# 3_phy1.net
KiCad netlist of a schematic drawn in Altium Designer
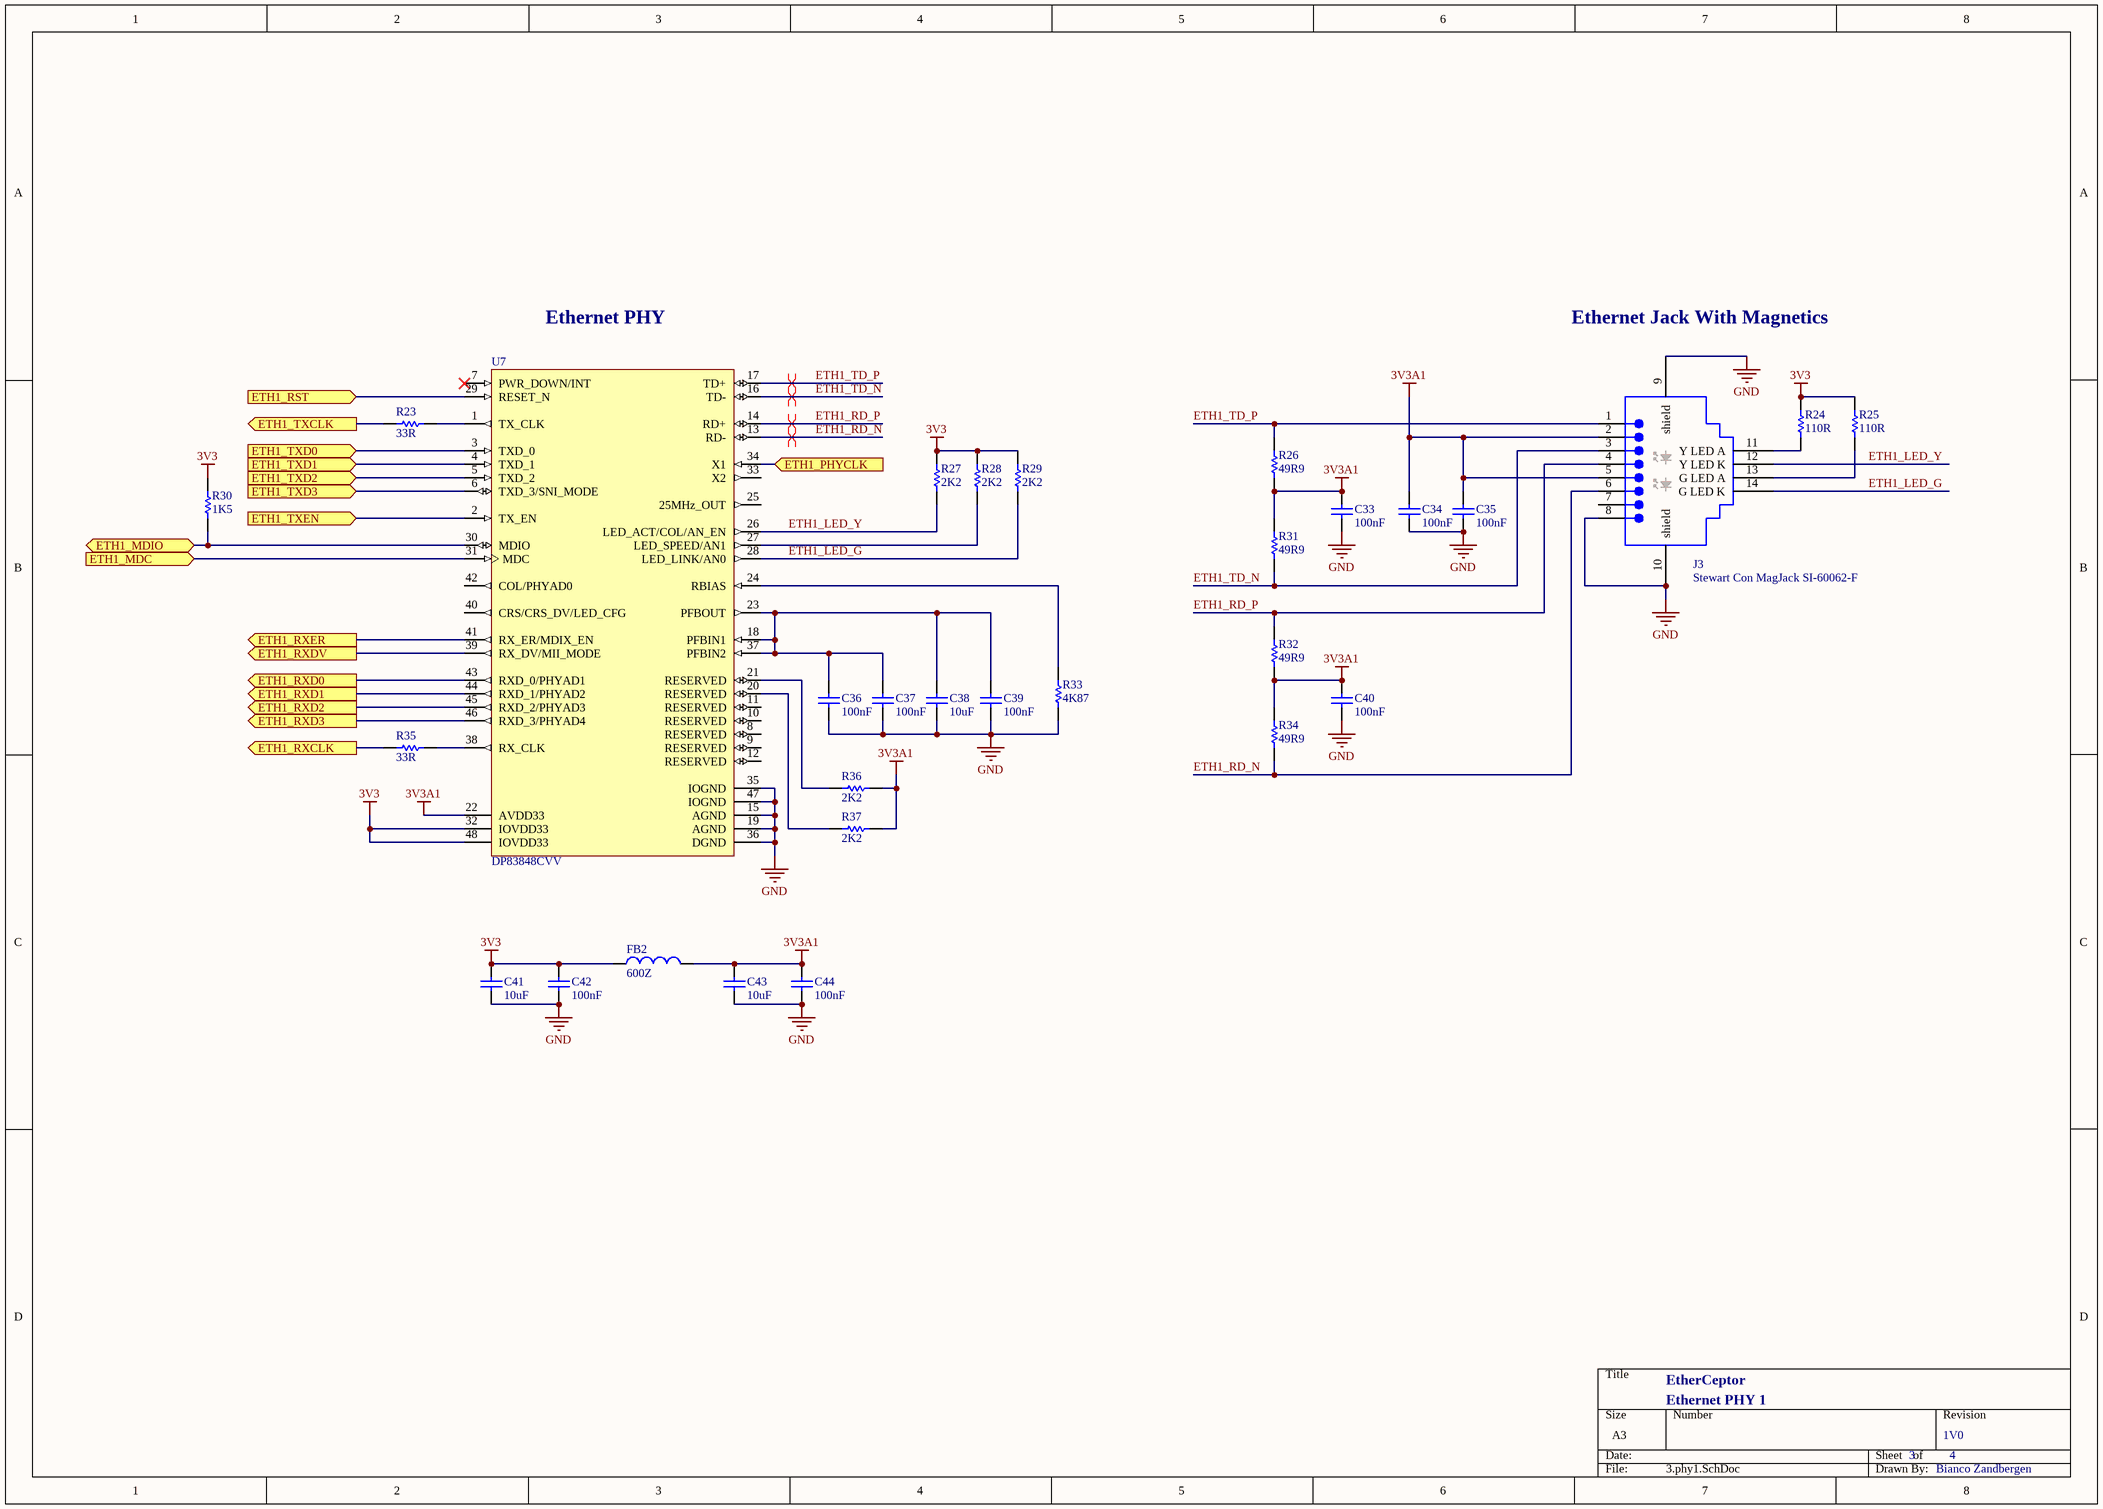
[diagram p0: 3.phy1.SchDoc]

(export (version "E")
  (design (tool "Eeschema 10.0.6"))
  (components
    (comp (ref "C33")
      (value "100nF")
      (footprint "1005[0402]_CAP2")
      (description "Capacitor")
      (fields
        (field (name "MANUFACTURER") "SAMSUNG")
        (field (name "Comment") "Cap")
        (field (name "PUBLISHER") "Altium Limited")
      )
      (libsource (lib "etherceptor") (part "Cap"))
    )
    (comp (ref "C34")
      (value "100nF")
      (footprint "1005[0402]_CAP2")
      (description "Capacitor")
      (fields
        (field (name "MANUFACTURER") "SAMSUNG")
        (field (name "Comment") "Cap")
        (field (name "PUBLISHER") "Altium Limited")
      )
      (libsource (lib "etherceptor") (part "Cap"))
    )
    (comp (ref "C35")
      (value "100nF")
      (footprint "1005[0402]_CAP2")
      (description "Capacitor")
      (fields
        (field (name "MANUFACTURER") "SAMSUNG")
        (field (name "Comment") "Cap")
        (field (name "PUBLISHER") "Altium Limited")
      )
      (libsource (lib "etherceptor") (part "Cap"))
    )
    (comp (ref "C36")
      (value "100nF")
      (footprint "1005[0402]_CAP2")
      (description "Capacitor")
      (fields
        (field (name "MANUFACTURER") "SAMSUNG")
        (field (name "Comment") "Cap")
        (field (name "PUBLISHER") "Altium Limited")
      )
      (libsource (lib "etherceptor") (part "Cap"))
    )
    (comp (ref "C37")
      (value "100nF")
      (footprint "1005[0402]_CAP2")
      (description "Capacitor")
      (fields
        (field (name "MANUFACTURER") "SAMSUNG")
        (field (name "Comment") "Cap")
        (field (name "PUBLISHER") "Altium Limited")
      )
      (libsource (lib "etherceptor") (part "Cap"))
    )
    (comp (ref "C38")
      (value "10uF")
      (footprint "1608[0603]_CAP2")
      (description "Capacitor")
      (fields
        (field (name "MANUFACTURER") "SAMSUNG")
        (field (name "Comment") "Cap")
        (field (name "PUBLISHER") "Altium Limited")
      )
      (libsource (lib "etherceptor") (part "Cap"))
    )
    (comp (ref "C39")
      (value "100nF")
      (footprint "1005[0402]_CAP2")
      (description "Capacitor")
      (fields
        (field (name "MANUFACTURER") "SAMSUNG")
        (field (name "Comment") "Cap")
        (field (name "PUBLISHER") "Altium Limited")
      )
      (libsource (lib "etherceptor") (part "Cap"))
    )
    (comp (ref "C40")
      (value "100nF")
      (footprint "1005[0402]_CAP2")
      (description "Capacitor")
      (fields
        (field (name "MANUFACTURER") "SAMSUNG")
        (field (name "Comment") "Cap")
        (field (name "PUBLISHER") "Altium Limited")
      )
      (libsource (lib "etherceptor") (part "Cap"))
    )
    (comp (ref "C41")
      (value "10uF")
      (footprint "1608[0603]_CAP2")
      (description "Capacitor")
      (fields
        (field (name "MANUFACTURER") "SAMSUNG")
        (field (name "Comment") "Cap")
        (field (name "PUBLISHER") "Altium Limited")
      )
      (libsource (lib "etherceptor") (part "Cap"))
    )
    (comp (ref "C42")
      (value "100nF")
      (footprint "1005[0402]_CAP2")
      (description "Capacitor")
      (fields
        (field (name "MANUFACTURER") "SAMSUNG")
        (field (name "Comment") "Cap")
        (field (name "PUBLISHER") "Altium Limited")
      )
      (libsource (lib "etherceptor") (part "Cap"))
    )
    (comp (ref "C43")
      (value "10uF")
      (footprint "1608[0603]_CAP2")
      (description "Capacitor")
      (fields
        (field (name "MANUFACTURER") "SAMSUNG")
        (field (name "Comment") "Cap")
        (field (name "PUBLISHER") "Altium Limited")
      )
      (libsource (lib "etherceptor") (part "Cap"))
    )
    (comp (ref "C44")
      (value "100nF")
      (footprint "1005[0402]_CAP2")
      (description "Capacitor")
      (fields
        (field (name "MANUFACTURER") "SAMSUNG")
        (field (name "Comment") "Cap")
        (field (name "PUBLISHER") "Altium Limited")
      )
      (libsource (lib "etherceptor") (part "Cap"))
    )
    (comp (ref "FB2")
      (value "600Z")
      (footprint "1005[0402]_FB2")
      (description "Ferrite Bead")
      (fields (field (name "MANUFACTURER") "MURATA") (field (name "PUBLISHER") "Altium Limited"))
      (libsource (lib "etherceptor") (part "Ferrite Bead"))
    )
    (comp (ref "J3")
      (value "Stewart Con MagJack SI-60062-F")
      (footprint "Steward Con RJ45")
      (description "Right Angle,RJ45-Keyed, Flange Mount PCB Jack")
      (fields (field (name "MANUFACTURER") "STEWART CONNECTOR") (field (name "PUBLISHER") "Altium Limited"))
      (libsource (lib "etherceptor") (part "Steward con RJ45 with magnetics"))
    )
    (comp (ref "R23")
      (value "33R")
      (footprint "1005[0402]_RES2")
      (description "Resistor")
      (fields
        (field (name "MANUFACTURER") "PANASONIC")
        (field (name "Comment") "Res")
        (field (name "PUBLISHER") "Altium Limited")
      )
      (libsource (lib "etherceptor") (part "Res"))
    )
    (comp (ref "R24")
      (value "110R")
      (footprint "1005[0402]_RES2")
      (description "Resistor")
      (fields
        (field (name "MANUFACTURER") "PANASONIC")
        (field (name "Comment") "Res")
        (field (name "PUBLISHER") "Altium Limited")
      )
      (libsource (lib "etherceptor") (part "Res"))
    )
    (comp (ref "R25")
      (value "110R")
      (footprint "1005[0402]_RES2")
      (description "Resistor")
      (fields
        (field (name "MANUFACTURER") "PANASONIC")
        (field (name "Comment") "Res")
        (field (name "PUBLISHER") "Altium Limited")
      )
      (libsource (lib "etherceptor") (part "Res"))
    )
    (comp (ref "R26")
      (value "49R9")
      (footprint "1005[0402]_RES2")
      (description "Resistor")
      (fields
        (field (name "MANUFACTURER") "PANASONIC")
        (field (name "Comment") "Res")
        (field (name "PUBLISHER") "Altium Limited")
      )
      (libsource (lib "etherceptor") (part "Res"))
    )
    (comp (ref "R27")
      (value "2K2")
      (footprint "1005[0402]_RES2")
      (description "Resistor")
      (fields
        (field (name "MANUFACTURER") "PANASONIC")
        (field (name "Comment") "Res")
        (field (name "PUBLISHER") "Altium Limited")
      )
      (libsource (lib "etherceptor") (part "Res"))
    )
    (comp (ref "R28")
      (value "2K2")
      (footprint "1005[0402]_RES2")
      (description "Resistor")
      (fields
        (field (name "MANUFACTURER") "PANASONIC")
        (field (name "Comment") "Res")
        (field (name "PUBLISHER") "Altium Limited")
      )
      (libsource (lib "etherceptor") (part "Res"))
    )
    (comp (ref "R29")
      (value "2K2")
      (footprint "1005[0402]_RES2")
      (description "Resistor")
      (fields
        (field (name "MANUFACTURER") "PANASONIC")
        (field (name "Comment") "Res")
        (field (name "PUBLISHER") "Altium Limited")
      )
      (libsource (lib "etherceptor") (part "Res"))
    )
    (comp (ref "R30")
      (value "1K5")
      (footprint "1005[0402]_RES2")
      (description "Resistor")
      (fields
        (field (name "MANUFACTURER") "PANASONIC")
        (field (name "Comment") "Res")
        (field (name "PUBLISHER") "Altium Limited")
      )
      (libsource (lib "etherceptor") (part "Res"))
    )
    (comp (ref "R31")
      (value "49R9")
      (footprint "1005[0402]_RES2")
      (description "Resistor")
      (fields
        (field (name "MANUFACTURER") "PANASONIC")
        (field (name "Comment") "Res")
        (field (name "PUBLISHER") "Altium Limited")
      )
      (libsource (lib "etherceptor") (part "Res"))
    )
    (comp (ref "R32")
      (value "49R9")
      (footprint "1005[0402]_RES2")
      (description "Resistor")
      (fields
        (field (name "MANUFACTURER") "PANASONIC")
        (field (name "Comment") "Res")
        (field (name "PUBLISHER") "Altium Limited")
      )
      (libsource (lib "etherceptor") (part "Res"))
    )
    (comp (ref "R33")
      (value "4K87")
      (footprint "1005[0402]_RES2")
      (description "Resistor")
      (fields
        (field (name "MANUFACTURER") "PANASONIC")
        (field (name "Comment") "Res")
        (field (name "PUBLISHER") "Altium Limited")
      )
      (libsource (lib "etherceptor") (part "Res"))
    )
    (comp (ref "R34")
      (value "49R9")
      (footprint "1005[0402]_RES2")
      (description "Resistor")
      (fields
        (field (name "MANUFACTURER") "PANASONIC")
        (field (name "Comment") "Res")
        (field (name "PUBLISHER") "Altium Limited")
      )
      (libsource (lib "etherceptor") (part "Res"))
    )
    (comp (ref "R35")
      (value "33R")
      (footprint "1005[0402]_RES2")
      (description "Resistor")
      (fields
        (field (name "MANUFACTURER") "PANASONIC")
        (field (name "Comment") "Res")
        (field (name "PUBLISHER") "Altium Limited")
      )
      (libsource (lib "etherceptor") (part "Res"))
    )
    (comp (ref "R36")
      (value "2K2")
      (footprint "1005[0402]_RES2")
      (description "Resistor")
      (fields
        (field (name "MANUFACTURER") "PANASONIC")
        (field (name "Comment") "Res")
        (field (name "PUBLISHER") "Altium Limited")
      )
      (libsource (lib "etherceptor") (part "Res"))
    )
    (comp (ref "R37")
      (value "2K2")
      (footprint "1005[0402]_RES2")
      (description "Resistor")
      (fields
        (field (name "MANUFACTURER") "PANASONIC")
        (field (name "Comment") "Res")
        (field (name "PUBLISHER") "Altium Limited")
      )
      (libsource (lib "etherceptor") (part "Res"))
    )
    (comp (ref "U7")
      (value "DP83848CVV")
      (footprint "TSQFP50P900X900-48M")
      (fields (field (name "MANUFACTURER") "TEXAS INSTRUMENTS") (field (name "PUBLISHER") "Altium Limited"))
      (libsource (lib "etherceptor") (part "DP83848CVV"))
    )
  )
  (nets
    (net (code "1") (name "/ETH1_LED_G") (class "Default")
      (node (ref "J3") (pin "14") (pinfunction "G_LED_K_14") (pintype "passive"))
      (node (ref "R29") (pin "1") (pinfunction "1_1") (pintype "passive"))
      (node (ref "U7") (pin "28") (pinfunction "LED_LINK/AN0_28") (pintype "output"))
    )
    (net (code "2") (name "/ETH1_LED_Y") (class "Default")
      (node (ref "J3") (pin "12") (pinfunction "Y_LED_K_12") (pintype "passive"))
      (node (ref "R27") (pin "1") (pinfunction "1_1") (pintype "passive"))
      (node (ref "U7") (pin "26") (pinfunction "LED_ACT/COL/AN_EN_26") (pintype "output"))
    )
    (net (code "3") (name "/ETH1_MDC") (class "Default")
      (node (ref "U7") (pin "31") (pinfunction "MDC_31") (pintype "input"))
    )
    (net (code "4") (name "/ETH1_MDIO") (class "Default")
      (node (ref "R30") (pin "1") (pinfunction "1_1") (pintype "passive"))
      (node (ref "U7") (pin "30") (pinfunction "MDIO_30") (pintype "bidirectional"))
    )
    (net (code "5") (name "/ETH1_PHYCLK") (class "Default")
      (node (ref "U7") (pin "34") (pinfunction "X1_34") (pintype "input"))
    )
    (net (code "6") (name "/ETH1_RD_N") (class "Default")
      (node (ref "J3") (pin "6") (pinfunction "6_6") (pintype "passive"))
      (node (ref "R34") (pin "1") (pinfunction "1_1") (pintype "passive"))
      (node (ref "U7") (pin "13") (pinfunction "RD-_13") (pintype "bidirectional"))
    )
    (net (code "7") (name "/ETH1_RD_P") (class "Default")
      (node (ref "J3") (pin "4") (pinfunction "4_4") (pintype "passive"))
      (node (ref "R32") (pin "2") (pinfunction "2_2") (pintype "passive"))
      (node (ref "U7") (pin "14") (pinfunction "RD+_14") (pintype "bidirectional"))
    )
    (net (code "8") (name "/ETH1_RST") (class "Default")
      (node (ref "U7") (pin "29") (pinfunction "RESET_N_29") (pintype "input"))
    )
    (net (code "9") (name "/ETH1_RXCLK") (class "Default")
      (node (ref "R35") (pin "1") (pinfunction "1_1") (pintype "passive"))
    )
    (net (code "10") (name "/ETH1_RXD0") (class "Default")
      (node (ref "U7") (pin "43") (pinfunction "RXD_0/PHYAD1_43") (pintype "output"))
    )
    (net (code "11") (name "/ETH1_RXD1") (class "Default")
      (node (ref "U7") (pin "44") (pinfunction "RXD_1/PHYAD2_44") (pintype "output"))
    )
    (net (code "12") (name "/ETH1_RXD2") (class "Default")
      (node (ref "U7") (pin "45") (pinfunction "RXD_2/PHYAD3_45") (pintype "output"))
    )
    (net (code "13") (name "/ETH1_RXD3") (class "Default")
      (node (ref "U7") (pin "46") (pinfunction "RXD_3/PHYAD4_46") (pintype "output"))
    )
    (net (code "14") (name "/ETH1_RXDV") (class "Default")
      (node (ref "U7") (pin "39") (pinfunction "RX_DV/MII_MODE_39") (pintype "output"))
    )
    (net (code "15") (name "/ETH1_RXER") (class "Default")
      (node (ref "U7") (pin "41") (pinfunction "RX_ER/MDIX_EN_41") (pintype "output"))
    )
    (net (code "16") (name "/ETH1_TD_N") (class "Default")
      (node (ref "J3") (pin "3") (pinfunction "3_3") (pintype "passive"))
      (node (ref "R31") (pin "1") (pinfunction "1_1") (pintype "passive"))
      (node (ref "U7") (pin "16") (pinfunction "TD-_16") (pintype "bidirectional"))
    )
    (net (code "17") (name "/ETH1_TD_P") (class "Default")
      (node (ref "J3") (pin "1") (pinfunction "1_1") (pintype "passive"))
      (node (ref "R26") (pin "2") (pinfunction "2_2") (pintype "passive"))
      (node (ref "U7") (pin "17") (pinfunction "TD+_17") (pintype "bidirectional"))
    )
    (net (code "18") (name "/ETH1_TXCLK") (class "Default")
      (node (ref "R23") (pin "1") (pinfunction "1_1") (pintype "passive"))
    )
    (net (code "19") (name "/ETH1_TXD0") (class "Default")
      (node (ref "U7") (pin "3") (pinfunction "TXD_0_3") (pintype "input"))
    )
    (net (code "20") (name "/ETH1_TXD1") (class "Default")
      (node (ref "U7") (pin "4") (pinfunction "TXD_1_4") (pintype "input"))
    )
    (net (code "21") (name "/ETH1_TXD2") (class "Default")
      (node (ref "U7") (pin "5") (pinfunction "TXD_2_5") (pintype "input"))
    )
    (net (code "22") (name "/ETH1_TXD3") (class "Default")
      (node (ref "U7") (pin "6") (pinfunction "TXD_3/SNI_MODE_6") (pintype "bidirectional"))
    )
    (net (code "23") (name "/ETH1_TXEN") (class "Default")
      (node (ref "U7") (pin "2") (pinfunction "TX_EN_2") (pintype "input"))
    )
    (net (code "24") (name "3V3") (class "Default")
      (node (ref "C41") (pin "2") (pinfunction "2_2") (pintype "passive"))
      (node (ref "C42") (pin "2") (pinfunction "2_2") (pintype "passive"))
      (node (ref "FB2") (pin "1") (pinfunction "1_1") (pintype "passive"))
      (node (ref "R24") (pin "2") (pinfunction "2_2") (pintype "passive"))
      (node (ref "R25") (pin "2") (pinfunction "2_2") (pintype "passive"))
      (node (ref "R27") (pin "2") (pinfunction "2_2") (pintype "passive"))
      (node (ref "R28") (pin "2") (pinfunction "2_2") (pintype "passive"))
      (node (ref "R29") (pin "2") (pinfunction "2_2") (pintype "passive"))
      (node (ref "R30") (pin "2") (pinfunction "2_2") (pintype "passive"))
      (node (ref "U7") (pin "32") (pinfunction "IOVDD33_32") (pintype "power_in"))
      (node (ref "U7") (pin "48") (pinfunction "IOVDD33_48") (pintype "power_in"))
    )
    (net (code "25") (name "3V3A1") (class "Default")
      (node (ref "C33") (pin "2") (pinfunction "2_2") (pintype "passive"))
      (node (ref "C34") (pin "2") (pinfunction "2_2") (pintype "passive"))
      (node (ref "C35") (pin "2") (pinfunction "2_2") (pintype "passive"))
      (node (ref "C40") (pin "2") (pinfunction "2_2") (pintype "passive"))
      (node (ref "C43") (pin "2") (pinfunction "2_2") (pintype "passive"))
      (node (ref "C44") (pin "2") (pinfunction "2_2") (pintype "passive"))
      (node (ref "FB2") (pin "2") (pinfunction "2_2") (pintype "passive"))
      (node (ref "J3") (pin "2") (pinfunction "2_2") (pintype "passive"))
      (node (ref "J3") (pin "5") (pinfunction "5_5") (pintype "passive"))
      (node (ref "R26") (pin "1") (pinfunction "1_1") (pintype "passive"))
      (node (ref "R31") (pin "2") (pinfunction "2_2") (pintype "passive"))
      (node (ref "R32") (pin "1") (pinfunction "1_1") (pintype "passive"))
      (node (ref "R34") (pin "2") (pinfunction "2_2") (pintype "passive"))
      (node (ref "R36") (pin "1") (pinfunction "1_1") (pintype "passive"))
      (node (ref "R37") (pin "1") (pinfunction "1_1") (pintype "passive"))
      (node (ref "U7") (pin "22") (pinfunction "AVDD33_22") (pintype "power_in"))
    )
    (net (code "26") (name "GND") (class "Default")
      (node (ref "C33") (pin "1") (pinfunction "1_1") (pintype "passive"))
      (node (ref "C34") (pin "1") (pinfunction "1_1") (pintype "passive"))
      (node (ref "C35") (pin "1") (pinfunction "1_1") (pintype "passive"))
      (node (ref "C36") (pin "1") (pinfunction "1_1") (pintype "passive"))
      (node (ref "C37") (pin "1") (pinfunction "1_1") (pintype "passive"))
      (node (ref "C38") (pin "1") (pinfunction "1_1") (pintype "passive"))
      (node (ref "C39") (pin "1") (pinfunction "1_1") (pintype "passive"))
      (node (ref "C40") (pin "1") (pinfunction "1_1") (pintype "passive"))
      (node (ref "C41") (pin "1") (pinfunction "1_1") (pintype "passive"))
      (node (ref "C42") (pin "1") (pinfunction "1_1") (pintype "passive"))
      (node (ref "C43") (pin "1") (pinfunction "1_1") (pintype "passive"))
      (node (ref "C44") (pin "1") (pinfunction "1_1") (pintype "passive"))
      (node (ref "J3") (pin "10") (pinfunction "shield_10") (pintype "passive"))
      (node (ref "J3") (pin "8") (pinfunction "8_8") (pintype "passive"))
      (node (ref "J3") (pin "9") (pinfunction "shield_9") (pintype "passive"))
      (node (ref "R33") (pin "1") (pinfunction "1_1") (pintype "passive"))
      (node (ref "U7") (pin "15") (pinfunction "AGND_15") (pintype "power_in"))
      (node (ref "U7") (pin "19") (pinfunction "AGND_19") (pintype "power_in"))
      (node (ref "U7") (pin "35") (pinfunction "IOGND_35") (pintype "power_in"))
      (node (ref "U7") (pin "36") (pinfunction "DGND_36") (pintype "power_in"))
      (node (ref "U7") (pin "47") (pinfunction "IOGND_47") (pintype "power_in"))
    )
    (net (code "27") (name "Net-(J3-G_LED_A)") (class "Default")
      (node (ref "J3") (pin "13") (pinfunction "G_LED_A_13") (pintype "passive"))
      (node (ref "R25") (pin "1") (pinfunction "1_1") (pintype "passive"))
    )
    (net (code "28") (name "Net-(J3-Y_LED_A)") (class "Default")
      (node (ref "J3") (pin "11") (pinfunction "Y_LED_A_11") (pintype "passive"))
      (node (ref "R24") (pin "1") (pinfunction "1_1") (pintype "passive"))
    )
    (net (code "29") (name "Net-(R36-Pad2)") (class "Default")
      (node (ref "R36") (pin "2") (pinfunction "2_2") (pintype "passive"))
      (node (ref "U7") (pin "21") (pinfunction "RESERVED_21") (pintype "bidirectional"))
    )
    (net (code "30") (name "Net-(R37-Pad2)") (class "Default")
      (node (ref "R37") (pin "2") (pinfunction "2_2") (pintype "passive"))
      (node (ref "U7") (pin "20") (pinfunction "RESERVED_20") (pintype "bidirectional"))
    )
    (net (code "31") (name "Net-(U7-LED_SPEED{slash}AN1)") (class "Default")
      (node (ref "R28") (pin "1") (pinfunction "1_1") (pintype "passive"))
      (node (ref "U7") (pin "27") (pinfunction "LED_SPEED/AN1_27") (pintype "output"))
    )
    (net (code "32") (name "Net-(U7-PFBIN1)") (class "Default")
      (node (ref "C36") (pin "2") (pinfunction "2_2") (pintype "passive"))
      (node (ref "C37") (pin "2") (pinfunction "2_2") (pintype "passive"))
      (node (ref "C38") (pin "2") (pinfunction "2_2") (pintype "passive"))
      (node (ref "C39") (pin "2") (pinfunction "2_2") (pintype "passive"))
      (node (ref "U7") (pin "18") (pinfunction "PFBIN1_18") (pintype "input"))
      (node (ref "U7") (pin "23") (pinfunction "PFBOUT_23") (pintype "output"))
      (node (ref "U7") (pin "37") (pinfunction "PFBIN2_37") (pintype "input"))
    )
    (net (code "33") (name "Net-(U7-RBIAS)") (class "Default")
      (node (ref "R33") (pin "2") (pinfunction "2_2") (pintype "passive"))
      (node (ref "U7") (pin "24") (pinfunction "RBIAS_24") (pintype "input"))
    )
    (net (code "34") (name "Net-(U7-RX_CLK)") (class "Default")
      (node (ref "R35") (pin "2") (pinfunction "2_2") (pintype "passive"))
      (node (ref "U7") (pin "38") (pinfunction "RX_CLK_38") (pintype "output"))
    )
    (net (code "35") (name "Net-(U7-TX_CLK)") (class "Default")
      (node (ref "R23") (pin "2") (pinfunction "2_2") (pintype "passive"))
      (node (ref "U7") (pin "1") (pinfunction "TX_CLK_1") (pintype "output"))
    )
    (net (code "36") (name "unconnected-(J3-Pad7)") (class "Default")
      (node (ref "J3") (pin "7") (pinfunction "7_7") (pintype "passive"))
    )
    (net (code "37") (name "unconnected-(U7-25MHz_OUT-Pad25)") (class "Default")
      (node (ref "U7") (pin "25") (pinfunction "25MHz_OUT_25") (pintype "output"))
    )
    (net (code "38") (name "unconnected-(U7-COL{slash}PHYAD0-Pad42)") (class "Default")
      (node (ref "U7") (pin "42") (pinfunction "COL/PHYAD0_42") (pintype "output"))
    )
    (net (code "39") (name "unconnected-(U7-CRS{slash}CRS_DV{slash}LED_CFG-Pad40)") (class "Default")
      (node (ref "U7") (pin "40") (pinfunction "CRS/CRS_DV/LED_CFG_40") (pintype "output"))
    )
    (net (code "40") (name "unconnected-(U7-PWR_DOWN{slash}INT-Pad7)") (class "Default")
      (node (ref "U7") (pin "7") (pinfunction "PWR_DOWN/INT_7") (pintype "input+no_connect"))
    )
    (net (code "41") (name "unconnected-(U7-RESERVED-Pad8)") (class "Default")
      (node (ref "U7") (pin "8") (pinfunction "RESERVED_8") (pintype "bidirectional"))
    )
    (net (code "42") (name "unconnected-(U7-RESERVED-Pad9)") (class "Default")
      (node (ref "U7") (pin "9") (pinfunction "RESERVED_9") (pintype "bidirectional"))
    )
    (net (code "43") (name "unconnected-(U7-RESERVED-Pad10)") (class "Default")
      (node (ref "U7") (pin "10") (pinfunction "RESERVED_10") (pintype "bidirectional"))
    )
    (net (code "44") (name "unconnected-(U7-RESERVED-Pad11)") (class "Default")
      (node (ref "U7") (pin "11") (pinfunction "RESERVED_11") (pintype "bidirectional"))
    )
    (net (code "45") (name "unconnected-(U7-RESERVED-Pad12)") (class "Default")
      (node (ref "U7") (pin "12") (pinfunction "RESERVED_12") (pintype "bidirectional"))
    )
    (net (code "46") (name "unconnected-(U7-X2-Pad33)") (class "Default")
      (node (ref "U7") (pin "33") (pinfunction "X2_33") (pintype "output"))
    )
  )
)
